# PumpDriver.net
KiCad netlist of a schematic drawn in Altium Designer
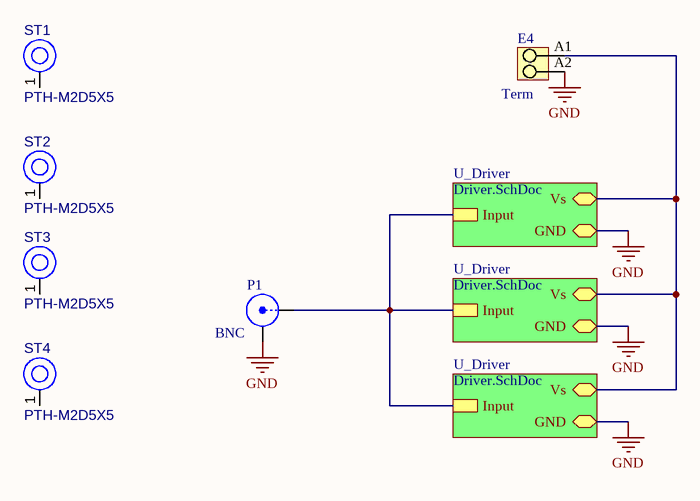
[diagram p0: PumpDriver.SchDoc]

(export (version "E")
  (design (tool "Eeschema 10.0.6"))
  (components
    (comp (ref "E4")
      (value "Term")
      (footprint "PM_5_08_90_02")
      (description "OMNIMATE Signal - series PM")
      (fields (field (name "MANUFACTURER") "Weidmueller") (field (name "PARTNUMBER") "1760490000"))
      (libsource (lib "Altium Content Vault") (part "Terminal_02_1x02"))
    )
    (comp (ref "P1")
      (value "BNC")
      (footprint "PWM_Over_Fiber_Receiver:TE_227161-1")
      (description "BNC Elbow Connector")
      (fields (field (name "PUBLISHER") "Altium Limited"))
      (libsource (lib "Miscellaneous Connectors") (part "BNC"))
    )
    (comp (ref "ST1")
      (value "PTH-M2D5X5")
      (footprint "PTH-M2D5X5")
      (description "M2 PTH (2.5mm), 5mm pad")
      (libsource (lib "National Institutes of Health-IDEAS") (part "CMP-00028-00000-1"))
    )
    (comp (ref "ST2")
      (value "PTH-M2D5X5")
      (footprint "PTH-M2D5X5")
      (description "M2 PTH (2.5mm), 5mm pad")
      (libsource (lib "National Institutes of Health-IDEAS") (part "CMP-00028-00000-1"))
    )
    (comp (ref "ST3")
      (value "PTH-M2D5X5")
      (footprint "PTH-M2D5X5")
      (description "M2 PTH (2.5mm), 5mm pad")
      (libsource (lib "National Institutes of Health-IDEAS") (part "CMP-00028-00000-1"))
    )
    (comp (ref "ST4")
      (value "PTH-M2D5X5")
      (footprint "PTH-M2D5X5")
      (description "M2 PTH (2.5mm), 5mm pad")
      (libsource (lib "National Institutes of Health-IDEAS") (part "CMP-00028-00000-1"))
    )
  )
  (nets
    (net (code "1") (name "/Input") (class "Default")
      (node (ref "P1") (pin "1") (pinfunction "X_1") (pintype "passive"))
    )
    (net (code "2") (name "/Vs") (class "Default")
      (node (ref "E4") (pin "A1") (pinfunction "A1_A1") (pintype "passive"))
    )
    (net (code "3") (name "GND") (class "Default")
      (node (ref "E4") (pin "A2") (pinfunction "A2_A2") (pintype "passive"))
      (node (ref "P1") (pin "2") (pinfunction "Y_2") (pintype "passive"))
    )
    (net (code "4") (name "unconnected-(ST1-H1-Pad1)") (class "Default")
      (node (ref "ST1") (pin "1") (pinfunction "H1_1") (pintype "passive"))
    )
    (net (code "5") (name "unconnected-(ST2-H1-Pad1)") (class "Default")
      (node (ref "ST2") (pin "1") (pinfunction "H1_1") (pintype "passive"))
    )
    (net (code "6") (name "unconnected-(ST3-H1-Pad1)") (class "Default")
      (node (ref "ST3") (pin "1") (pinfunction "H1_1") (pintype "passive"))
    )
    (net (code "7") (name "unconnected-(ST4-H1-Pad1)") (class "Default")
      (node (ref "ST4") (pin "1") (pinfunction "H1_1") (pintype "passive"))
    )
  )
)
